# design.net
KiCad netlist of a schematic drawn in Altium Designer
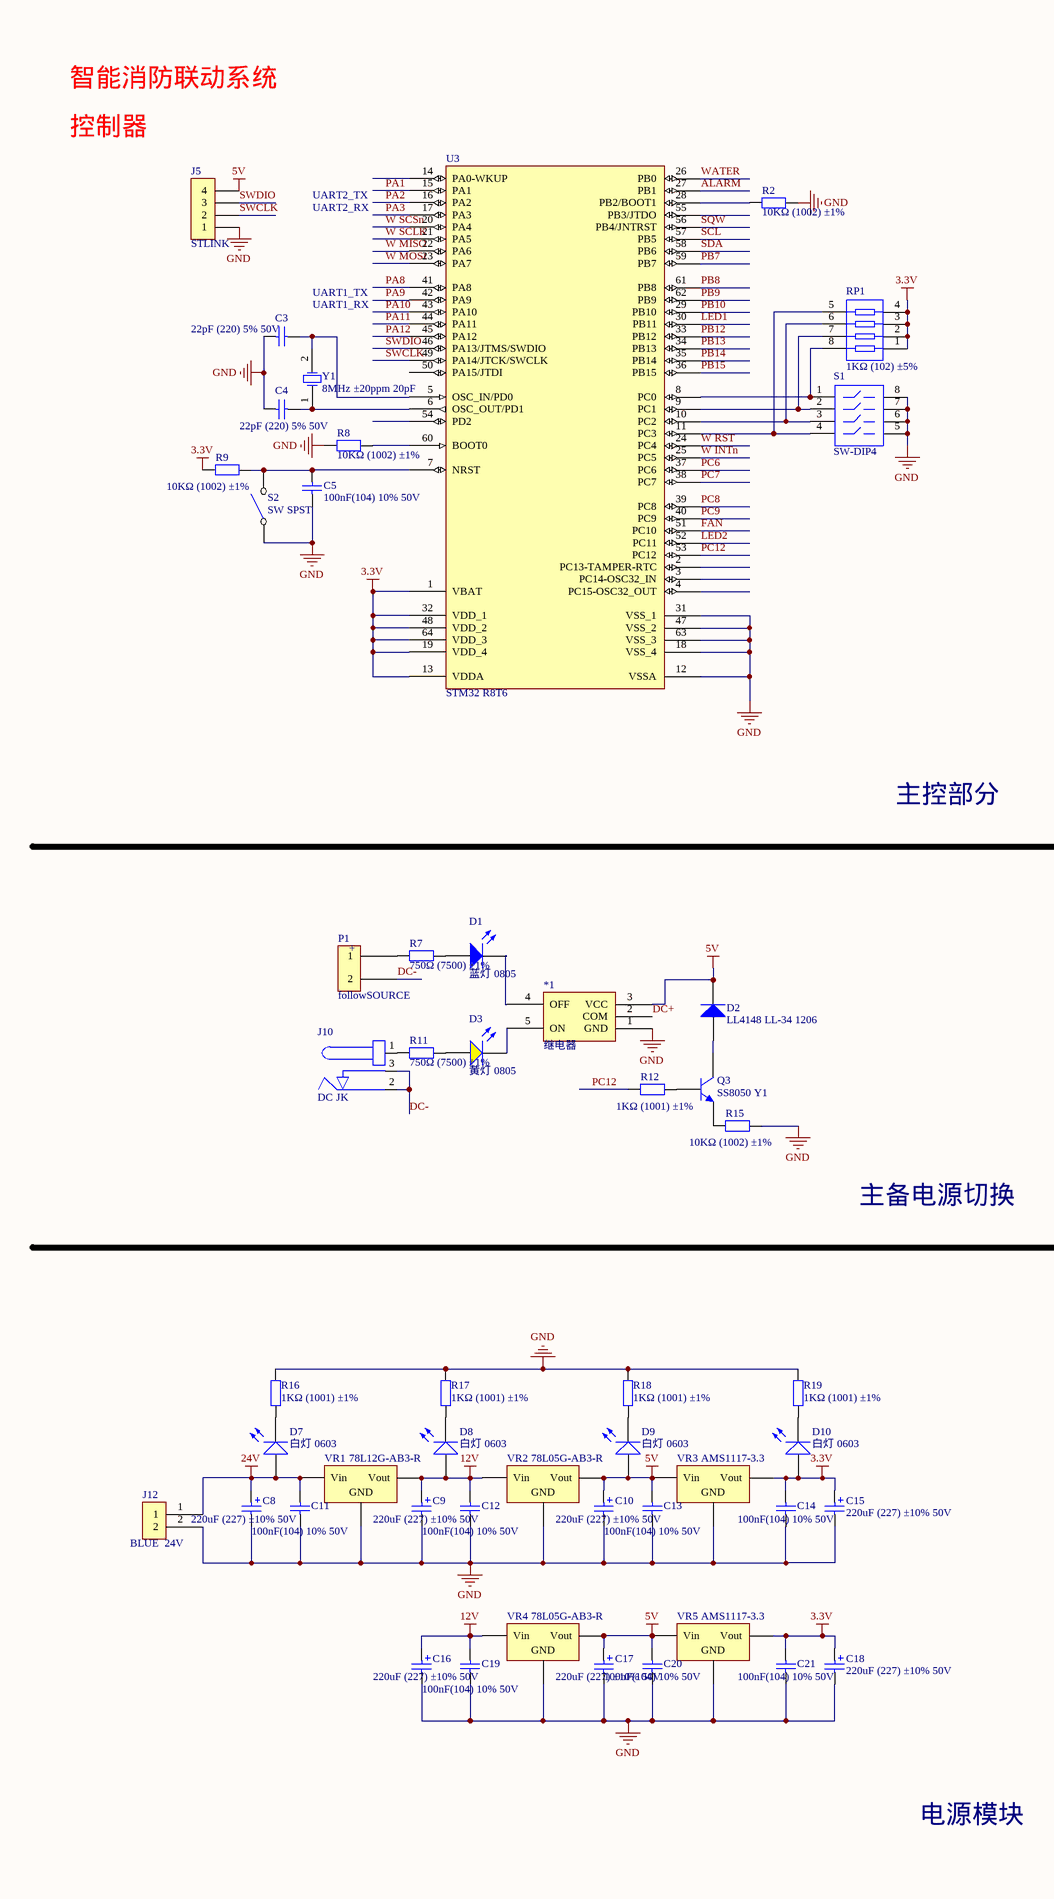
[diagram p0: 控制器.SchDoc, left]
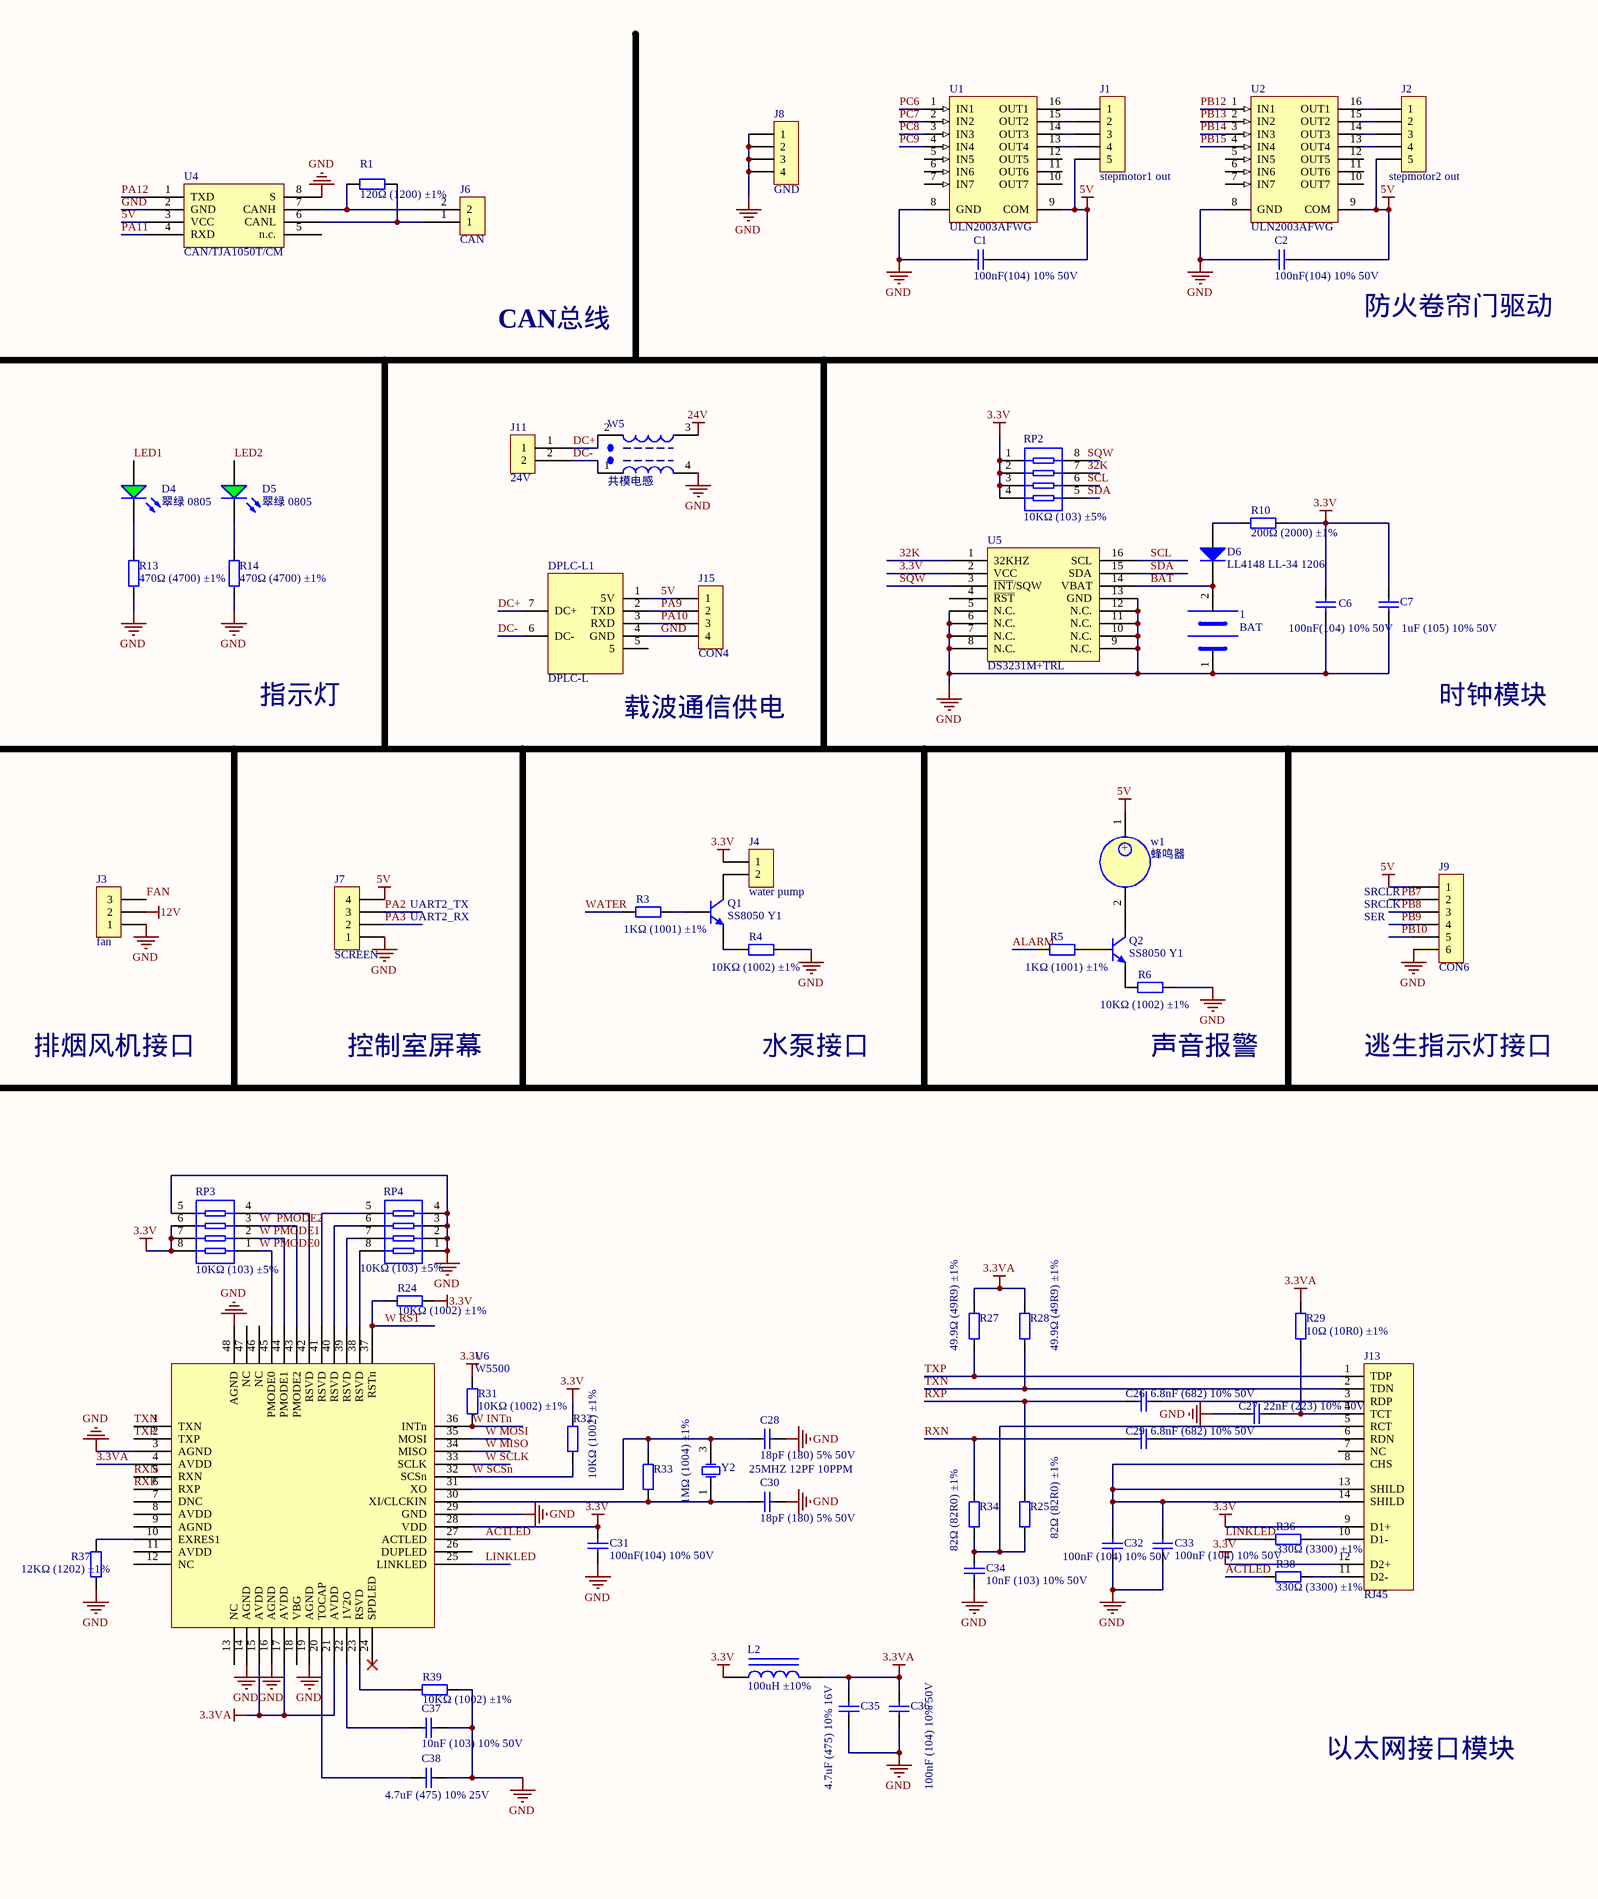
[diagram p1: 控制器.SchDoc, right]

(export (version "E")
  (design (tool "Eeschema 10.0.6"))
  (components
    (comp (ref "*1") (value "继电器") (footprint "RLY-964") (libsource (lib "毕设原理图封装库") (part "继电器")))
    (comp (ref "1") (value "BAT") (footprint "BAT") (libsource (lib "毕设原理图封装库") (part "BAT")))
    (comp (ref "C1")
      (value "100nF(104) 10% 50V")
      (footprint "LC-0805_C")
      (description "贴片电容")
      (libsource (lib "Miscellaneous Devices LC") (part "0805 100nF(104) 10% 50V"))
    )
    (comp (ref "C2")
      (value "100nF(104) 10% 50V")
      (footprint "LC-0805_C")
      (description "贴片电容")
      (libsource (lib "Miscellaneous Devices LC") (part "0805 100nF(104) 10% 50V"))
    )
    (comp (ref "C3")
      (value "22pF (220) 5% 50V")
      (footprint "LC-0805_C")
      (description "贴片电容")
      (libsource (lib "Miscellaneous Devices LC") (part "0805 22pF (220) 5% 50V"))
    )
    (comp (ref "C4")
      (value "22pF (220) 5% 50V")
      (footprint "LC-0805_C")
      (description "贴片电容")
      (libsource (lib "Miscellaneous Devices LC") (part "0805 22pF (220) 5% 50V"))
    )
    (comp (ref "C5")
      (value "100nF(104) 10% 50V")
      (footprint "LC-0805_C")
      (description "贴片电容")
      (libsource (lib "Miscellaneous Devices LC") (part "0805 100nF(104) 10% 50V"))
    )
    (comp (ref "C6")
      (value "100nF(104) 10% 50V")
      (footprint "LC-0805_C")
      (description "贴片电容")
      (libsource (lib "Miscellaneous Devices LC") (part "0805 100nF(104) 10% 50V"))
    )
    (comp (ref "C7")
      (value "1uF (105) 10% 50V")
      (footprint "LC-0805_C")
      (description "贴片电容")
      (libsource (lib "Miscellaneous Devices LC") (part "0805 1uF (105) 10% 50V"))
    )
    (comp (ref "C8")
      (value "220uF (227) ±10% 50V")
      (footprint "LC-CASE-B_3528")
      (description "钽电容")
      (libsource (lib "") (part "3528 100uF (107) 10% 6.3V_1"))
    )
    (comp (ref "C9")
      (value "220uF (227) ±10% 50V")
      (footprint "LC-CASE-B_3528")
      (description "钽电容")
      (libsource (lib "") (part "3528 100uF (107) 10% 6.3V_1"))
    )
    (comp (ref "C10")
      (value "220uF (227) ±10% 50V")
      (footprint "LC-CASE-B_3528")
      (description "钽电容")
      (libsource (lib "") (part "3528 100uF (107) 10% 6.3V_1"))
    )
    (comp (ref "C11")
      (value "100nF(104) 10% 50V")
      (footprint "LC-0805_C")
      (description "贴片电容")
      (libsource (lib "Miscellaneous Devices LC") (part "0805 100nF(104) 10% 50V"))
    )
    (comp (ref "C12")
      (value "100nF(104) 10% 50V")
      (footprint "LC-0805_C")
      (description "贴片电容")
      (libsource (lib "Miscellaneous Devices LC") (part "0805 100nF(104) 10% 50V"))
    )
    (comp (ref "C13")
      (value "100nF(104) 10% 50V")
      (footprint "LC-0805_C")
      (description "贴片电容")
      (libsource (lib "Miscellaneous Devices LC") (part "0805 100nF(104) 10% 50V"))
    )
    (comp (ref "C14")
      (value "100nF(104) 10% 50V")
      (footprint "LC-0805_C")
      (description "贴片电容")
      (libsource (lib "Miscellaneous Devices LC") (part "0805 100nF(104) 10% 50V"))
    )
    (comp (ref "C15")
      (value "220uF (227) ±10% 50V")
      (footprint "LC-CASE-B_3528")
      (description "钽电容")
      (libsource (lib "") (part "3528 100uF (107) 10% 6.3V_1"))
    )
    (comp (ref "C16")
      (value "220uF (227) ±10% 50V")
      (footprint "LC-CASE-B_3528")
      (description "钽电容")
      (libsource (lib "") (part "3528 100uF (107) 10% 6.3V_1"))
    )
    (comp (ref "C17")
      (value "220uF (227) ±10% 50V")
      (footprint "LC-CASE-B_3528")
      (description "钽电容")
      (libsource (lib "") (part "3528 100uF (107) 10% 6.3V_1"))
    )
    (comp (ref "C18")
      (value "220uF (227) ±10% 50V")
      (footprint "LC-CASE-B_3528")
      (description "钽电容")
      (libsource (lib "Miscellaneous Devices LC") (part "3528 100uF (107) 10% 6.3V"))
    )
    (comp (ref "C19")
      (value "100nF(104) 10% 50V")
      (footprint "LC-0805_C")
      (description "贴片电容")
      (libsource (lib "Miscellaneous Devices LC") (part "0805 100nF(104) 10% 50V"))
    )
    (comp (ref "C20")
      (value "100nF(104) 10% 50V")
      (footprint "LC-0805_C")
      (description "贴片电容")
      (libsource (lib "Miscellaneous Devices LC") (part "0805 100nF(104) 10% 50V"))
    )
    (comp (ref "C21")
      (value "100nF(104) 10% 50V")
      (footprint "LC-0805_C")
      (description "贴片电容")
      (libsource (lib "Miscellaneous Devices LC") (part "0805 100nF(104) 10% 50V"))
    )
    (comp (ref "C26")
      (value "6.8nF (682) 10% 50V")
      (footprint "LC-0603_C")
      (description "贴片电容")
      (libsource (lib "Miscellaneous Devices LC") (part "0603 6.8nF (682) 10% 50V"))
    )
    (comp (ref "C27")
      (value "22nF (223) 10% 50V")
      (footprint "LC-0603_C")
      (description "贴片电容")
      (libsource (lib "Miscellaneous Devices LC") (part "0603 22nF (223) 10% 50V"))
    )
    (comp (ref "C28")
      (value "18pF (180) 5% 50V")
      (footprint "LC-0805_C")
      (description "贴片电容")
      (libsource (lib "Miscellaneous Devices LC") (part "0805 18pF (180) 5% 50V"))
    )
    (comp (ref "C29")
      (value "6.8nF (682) 10% 50V")
      (footprint "LC-0603_C")
      (description "贴片电容")
      (libsource (lib "Miscellaneous Devices LC") (part "0603 6.8nF (682) 10% 50V"))
    )
    (comp (ref "C30")
      (value "18pF (180) 5% 50V")
      (footprint "LC-0805_C")
      (description "贴片电容")
      (libsource (lib "Miscellaneous Devices LC") (part "0805 18pF (180) 5% 50V"))
    )
    (comp (ref "C31")
      (value "100nF(104) 10% 50V")
      (footprint "LC-0805_C")
      (description "贴片电容")
      (libsource (lib "Miscellaneous Devices LC") (part "0805 100nF(104) 10% 50V"))
    )
    (comp (ref "C32")
      (value "100nF (104) 10% 50V")
      (footprint "LC-0603_C")
      (description "贴片电容")
      (libsource (lib "Miscellaneous Devices LC") (part "0603 100nF (104) 10% 50V"))
    )
    (comp (ref "C33")
      (value "100nF (104) 10% 50V")
      (footprint "LC-0603_C")
      (description "贴片电容")
      (libsource (lib "Miscellaneous Devices LC") (part "0603 100nF (104) 10% 50V"))
    )
    (comp (ref "C34")
      (value "10nF (103) 10% 50V")
      (footprint "LC-0603_C")
      (description "贴片电容")
      (libsource (lib "Miscellaneous Devices LC") (part "0603 10nF (103) 10% 50V"))
    )
    (comp (ref "C35")
      (value "4.7uF (475) 10% 16V")
      (footprint "LC-0603_C")
      (description "贴片电容")
      (libsource (lib "Miscellaneous Devices LC") (part "0603 4.7uF (475) 10% 16V"))
    )
    (comp (ref "C36")
      (value "100nF (104) 10% 50V")
      (footprint "LC-0603_C")
      (description "贴片电容")
      (libsource (lib "Miscellaneous Devices LC") (part "0603 100nF (104) 10% 50V"))
    )
    (comp (ref "C37")
      (value "10nF (103) 10% 50V")
      (footprint "LC-0805_C")
      (description "贴片电容")
      (libsource (lib "Miscellaneous Devices LC") (part "0805 10nF (103) 10% 50V"))
    )
    (comp (ref "C38")
      (value "4.7uF (475) 10% 25V")
      (footprint "LC-0805_C")
      (description "贴片电容")
      (libsource (lib "Miscellaneous Devices LC") (part "0805 4.7uF (475) 10% 25V"))
    )
    (comp (ref "D1")
      (value "蓝灯 0805")
      (footprint "LC-0805_LED_S1")
      (description "发光二极管")
      (libsource (lib "Miscellaneous Devices LC") (part "0805 蓝灯"))
    )
    (comp (ref "D2")
      (value "LL4148 LL-34 1206")
      (footprint "LC-LL-34")
      (description "开关二极管")
      (libsource (lib "Miscellaneous Devices LC") (part "LL-34 LL4148 LL-34 1206"))
    )
    (comp (ref "D3")
      (value "黄灯 0805")
      (footprint "LC-0805_LED_S1")
      (description "发光二极管")
      (libsource (lib "Miscellaneous Devices LC") (part "0805 黄灯"))
    )
    (comp (ref "D4")
      (value "翠绿 0805")
      (footprint "LC-0805_LED_S1")
      (description "发光二极管")
      (libsource (lib "Miscellaneous Devices LC") (part "0805 翠绿"))
    )
    (comp (ref "D5")
      (value "翠绿 0805")
      (footprint "LC-0805_LED_S1")
      (description "发光二极管")
      (libsource (lib "Miscellaneous Devices LC") (part "0805 翠绿"))
    )
    (comp (ref "D6")
      (value "LL4148 LL-34 1206")
      (footprint "LC-LL-34")
      (description "开关二极管")
      (libsource (lib "Miscellaneous Devices LC") (part "LL-34 LL4148 LL-34 1206"))
    )
    (comp (ref "D7")
      (value "白灯 0603")
      (footprint "LC-0603_LED_S1")
      (description "发光二极管")
      (libsource (lib "Miscellaneous Devices LC") (part "0603 白灯"))
    )
    (comp (ref "D8")
      (value "白灯 0603")
      (footprint "LC-0603_LED_S1")
      (description "发光二极管")
      (libsource (lib "Miscellaneous Devices LC") (part "0603 白灯"))
    )
    (comp (ref "D9")
      (value "白灯 0603")
      (footprint "LC-0603_LED_S1")
      (description "发光二极管")
      (libsource (lib "Miscellaneous Devices LC") (part "0603 白灯"))
    )
    (comp (ref "D10")
      (value "白灯 0603")
      (footprint "LC-0603_LED_S1")
      (description "发光二极管")
      (libsource (lib "Miscellaneous Devices LC") (part "0603 白灯"))
    )
    (comp (ref "DPLC-L1") (value "DPLC-L") (footprint "DPLC-L") (libsource (lib "毕设原理图封装库") (part "DPLC-L")))
    (comp (ref "J1") (value "stepmotor1 out") (footprint "防反插乘5") (libsource (lib "原理图封装库") (part "CON5")))
    (comp (ref "J2") (value "stepmotor2 out") (footprint "防反插乘5") (libsource (lib "原理图封装库") (part "CON5")))
    (comp (ref "J3") (value "fan") (footprint "SIP3") (libsource (lib "原理图封装库") (part "CON3")))
    (comp (ref "J4") (value "water pump") (footprint "SIP2") (libsource (lib "原理图封装库") (part "CON2")))
    (comp (ref "J5") (value "STLINK") (footprint "SIP4") (libsource (lib "毕设原理图封装库") (part "CON4")))
    (comp (ref "J6") (value "CAN") (footprint "蓝端子") (libsource (lib "") (part "蓝端子_2")))
    (comp (ref "J7") (value "SCREEN") (footprint "SIP4") (libsource (lib "毕设原理图封装库") (part "CON4")))
    (comp (ref "J8") (value "GND") (footprint "SIP4") (libsource (lib "") (part "CON4_1")))
    (comp (ref "J9") (value "CON6") (footprint "SIP6") (libsource (lib "毕设原理图封装库") (part "CON6")))
    (comp (ref "J10") (value "DC JK") (footprint "DC") (libsource (lib "Backup of 耳机座") (part "DC JK")))
    (comp (ref "J11") (value "24V") (footprint "蓝端子") (libsource (lib "毕设原理图封装库") (part "蓝端子")))
    (comp (ref "J12") (value "BLUE  24V") (footprint "蓝端子") (libsource (lib "毕设原理图封装库") (part "蓝端子")))
    (comp (ref "J13") (value "RJ45") (footprint "RJ-45_GBE") (libsource (lib "毕设原理图封装库") (part "RJ45")))
    (comp (ref "J15") (value "CON4") (footprint "SIP4") (libsource (lib "") (part "CON4_1")))
    (comp (ref "L2")
      (value "100uH ±10%")
      (footprint "LC-0805_L")
      (description "贴片电感")
      (libsource (lib "Miscellaneous Devices LC") (part "0805 100uH 10%"))
    )
    (comp (ref "P1") (value "followSOURCE") (footprint "蓝端子") (libsource (lib "") (part "蓝端子_1")))
    (comp (ref "Q1")
      (value "SS8050 Y1")
      (footprint "LC-SOT-23(SOT-23-3)")
      (description "三极管")
      (libsource (lib "Miscellaneous Devices LC") (part "SOT-23 SS8050 Y1"))
    )
    (comp (ref "Q2")
      (value "SS8050 Y1")
      (footprint "LC-SOT-23(SOT-23-3)")
      (description "三极管")
      (libsource (lib "Miscellaneous Devices LC") (part "SOT-23 SS8050 Y1"))
    )
    (comp (ref "Q3")
      (value "SS8050 Y1")
      (footprint "LC-SOT-23(SOT-23-3)")
      (description "三极管")
      (libsource (lib "Miscellaneous Devices LC") (part "SOT-23 SS8050 Y1"))
    )
    (comp (ref "R1")
      (value "120Ω (1200) ±1%")
      (footprint "LC-0805_R")
      (description "贴片电阻")
      (libsource (lib "Miscellaneous Devices LC") (part "0805 120Ω (1200) 1%"))
    )
    (comp (ref "R2")
      (value "10KΩ (1002) ±1%")
      (footprint "LC-0805_R")
      (description "贴片电阻")
      (libsource (lib "Miscellaneous Devices LC") (part "0805 10KΩ (1002) 1%"))
    )
    (comp (ref "R3")
      (value "1KΩ (1001) ±1%")
      (footprint "LC-0805_R")
      (description "贴片电阻")
      (libsource (lib "Miscellaneous Devices LC") (part "0805 1KΩ (1001) 1%"))
    )
    (comp (ref "R4")
      (value "10KΩ (1002) ±1%")
      (footprint "LC-0805_R")
      (description "贴片电阻")
      (libsource (lib "Miscellaneous Devices LC") (part "0805 10KΩ (1002) 1%"))
    )
    (comp (ref "R5")
      (value "1KΩ (1001) ±1%")
      (footprint "LC-0805_R")
      (description "贴片电阻")
      (libsource (lib "Miscellaneous Devices LC") (part "0805 1KΩ (1001) 1%"))
    )
    (comp (ref "R6")
      (value "10KΩ (1002) ±1%")
      (footprint "LC-0805_R")
      (description "贴片电阻")
      (libsource (lib "Miscellaneous Devices LC") (part "0805 10KΩ (1002) 1%"))
    )
    (comp (ref "R7")
      (value "750Ω (7500) ±1%")
      (footprint "LC-0805_R")
      (description "贴片电阻")
      (libsource (lib "Miscellaneous Devices LC") (part "0805 750Ω (7500) 1%"))
    )
    (comp (ref "R8")
      (value "10KΩ (1002) ±1%")
      (footprint "LC-0805_R")
      (description "贴片电阻")
      (libsource (lib "Miscellaneous Devices LC") (part "0805 10KΩ (1002) 1%"))
    )
    (comp (ref "R9")
      (value "10KΩ (1002) ±1%")
      (footprint "LC-0805_R")
      (description "贴片电阻")
      (libsource (lib "Miscellaneous Devices LC") (part "0805 10KΩ (1002) 1%"))
    )
    (comp (ref "R10")
      (value "200Ω (2000) ±1%")
      (footprint "LC-0805_R")
      (description "贴片电阻")
      (libsource (lib "Miscellaneous Devices LC") (part "0805 200Ω (2000) 1%"))
    )
    (comp (ref "R11")
      (value "750Ω (7500) ±1%")
      (footprint "LC-0805_R")
      (description "贴片电阻")
      (libsource (lib "Miscellaneous Devices LC") (part "0805 750Ω (7500) 1%"))
    )
    (comp (ref "R12")
      (value "1KΩ (1001) ±1%")
      (footprint "LC-0805_R")
      (description "贴片电阻")
      (libsource (lib "Miscellaneous Devices LC") (part "0805 1KΩ (1001) 1%"))
    )
    (comp (ref "R13")
      (value "470Ω (4700) ±1%")
      (footprint "LC-0805_R")
      (description "贴片电阻")
      (libsource (lib "Miscellaneous Devices LC") (part "0805 470Ω (4700) 1%"))
    )
    (comp (ref "R14")
      (value "470Ω (4700) ±1%")
      (footprint "LC-0805_R")
      (description "贴片电阻")
      (libsource (lib "Miscellaneous Devices LC") (part "0805 470Ω (4700) 1%"))
    )
    (comp (ref "R15")
      (value "10KΩ (1002) ±1%")
      (footprint "LC-0805_R")
      (description "贴片电阻")
      (libsource (lib "Miscellaneous Devices LC") (part "0805 10KΩ (1002) 1%"))
    )
    (comp (ref "R16")
      (value "1KΩ (1001) ±1%")
      (footprint "LC-0603_R")
      (description "贴片电阻")
      (libsource (lib "Miscellaneous Devices LC") (part "0603 1KΩ (1001) 1%"))
    )
    (comp (ref "R17")
      (value "1KΩ (1001) ±1%")
      (footprint "LC-0603_R")
      (description "贴片电阻")
      (libsource (lib "Miscellaneous Devices LC") (part "0603 1KΩ (1001) 1%"))
    )
    (comp (ref "R18")
      (value "1KΩ (1001) ±1%")
      (footprint "LC-0603_R")
      (description "贴片电阻")
      (libsource (lib "Miscellaneous Devices LC") (part "0603 1KΩ (1001) 1%"))
    )
    (comp (ref "R19")
      (value "1KΩ (1001) ±1%")
      (footprint "LC-0603_R")
      (description "贴片电阻")
      (libsource (lib "Miscellaneous Devices LC") (part "0603 1KΩ (1001) 1%"))
    )
    (comp (ref "R24")
      (value "10KΩ (1002) ±1%")
      (footprint "LC-0805_R")
      (description "贴片电阻")
      (libsource (lib "Miscellaneous Devices LC") (part "0805 10KΩ (1002) 1%"))
    )
    (comp (ref "R25")
      (value "82Ω (82R0) ±1%")
      (footprint "LC-0603_R")
      (description "贴片电阻")
      (libsource (lib "Miscellaneous Devices LC") (part "0603 82Ω (82R0) 1%"))
    )
    (comp (ref "R27")
      (value "49.9Ω (49R9) ±1%")
      (footprint "LC-0603_R")
      (description "贴片电阻")
      (libsource (lib "Miscellaneous Devices LC") (part "0603 49.9Ω (49R9) 1%"))
    )
    (comp (ref "R28")
      (value "49.9Ω (49R9) ±1%")
      (footprint "LC-0603_R")
      (description "贴片电阻")
      (libsource (lib "Miscellaneous Devices LC") (part "0603 49.9Ω (49R9) 1%"))
    )
    (comp (ref "R29")
      (value "10Ω (10R0) ±1%")
      (footprint "LC-0805_R")
      (description "贴片电阻")
      (libsource (lib "Miscellaneous Devices LC") (part "0805 10Ω (10R0) 1%"))
    )
    (comp (ref "R31")
      (value "10KΩ (1002) ±1%")
      (footprint "LC-0805_R")
      (description "贴片电阻")
      (libsource (lib "") (part "0805 10KΩ (1002) 1%_1"))
    )
    (comp (ref "R32")
      (value "10KΩ (1002) ±1%")
      (footprint "LC-0805_R")
      (description "贴片电阻")
      (libsource (lib "") (part "0805 10KΩ (1002) 1%_1"))
    )
    (comp (ref "R33")
      (value "1MΩ (1004) ±1%")
      (footprint "LC-0805_R")
      (description "贴片电阻")
      (libsource (lib "Miscellaneous Devices LC") (part "0805 1MΩ (1004) 1%"))
    )
    (comp (ref "R34")
      (value "82Ω (82R0) ±1%")
      (footprint "LC-0603_R")
      (description "贴片电阻")
      (libsource (lib "Miscellaneous Devices LC") (part "0603 82Ω (82R0) 1%"))
    )
    (comp (ref "R36")
      (value "330Ω (3300) ±1%")
      (footprint "LC-0603_R")
      (description "贴片电阻")
      (libsource (lib "Miscellaneous Devices LC") (part "0603 330Ω (3300) 1%"))
    )
    (comp (ref "R37")
      (value "12KΩ (1202) ±1%")
      (footprint "LC-0805_R")
      (description "贴片电阻")
      (libsource (lib "Miscellaneous Devices LC") (part "0805 12KΩ (1202) 1%"))
    )
    (comp (ref "R38")
      (value "330Ω (3300) ±1%")
      (footprint "LC-0603_R")
      (description "贴片电阻")
      (libsource (lib "Miscellaneous Devices LC") (part "0603 330Ω (3300) 1%"))
    )
    (comp (ref "R39")
      (value "10KΩ (1002) ±1%")
      (footprint "LC-0805_R")
      (description "贴片电阻")
      (libsource (lib "Miscellaneous Devices LC") (part "0805 10KΩ (1002) 1%"))
    )
    (comp (ref "RP1")
      (value "1KΩ (102) ±5%")
      (footprint "LC-0603_Rx4")
      (description "贴片排阻")
      (libsource (lib "Miscellaneous Devices LC") (part "0603*4  1KΩ (102) 5%"))
    )
    (comp (ref "RP2")
      (value "10KΩ (103) ±5%")
      (footprint "LC-0603_Rx4")
      (description "贴片排阻")
      (libsource (lib "Miscellaneous Devices LC") (part "0603*4  10KΩ (103) 5%"))
    )
    (comp (ref "RP3")
      (value "10KΩ (103) ±5%")
      (footprint "LC-0603_Rx4")
      (description "贴片排阻")
      (libsource (lib "Miscellaneous Devices LC") (part "0603*4  10KΩ (103) 5%"))
    )
    (comp (ref "RP4")
      (value "10KΩ (103) ±5%")
      (footprint "LC-0603_Rx4")
      (description "贴片排阻")
      (libsource (lib "Miscellaneous Devices LC") (part "0603*4  10KΩ (103) 5%"))
    )
    (comp (ref "S1")
      (value "SW-DIP4")
      (footprint "4位拨码开关")
      (description "4位拨码开关")
      (libsource (lib "毕设原理图封装库") (part "SW-DIP4"))
    )
    (comp (ref "S2")
      (value "SW SPST")
      (footprint "单片机小按键")
      (description "单刀单掷开关")
      (libsource (lib "毕设原理图封装库") (part "SW SPST"))
    )
    (comp (ref "U1")
      (value "ULN2003AFWG")
      (footprint "LC-SOIC-16_150mil")
      (description "大电流驱动")
      (libsource (lib "Miscellaneous Devices LC") (part "ULN2003AFWG"))
    )
    (comp (ref "U2")
      (value "ULN2003AFWG")
      (footprint "LC-SOIC-16_150mil")
      (description "大电流驱动")
      (libsource (lib "Miscellaneous Devices LC") (part "ULN2003AFWG"))
    )
    (comp (ref "U3")
      (value "STM32 R8T6")
      (footprint "LC-LQFP-64_10x10x05P")
      (libsource (lib "毕设原理图封装库") (part "STM32 R8T6"))
    )
    (comp (ref "U4")
      (value "CAN/TJA1050T/CM")
      (footprint "LC-SOIC-8_150mil")
      (description "CAN")
      (libsource (lib "Miscellaneous Devices LC") (part "CAN/TJA1050T/CM"))
    )
    (comp (ref "U5")
      (value "DS3231M+TRL")
      (footprint "LC-SOIC-16_300mil")
      (description "实时时钟")
      (libsource (lib "Miscellaneous Devices LC") (part "DS3231M+TRL"))
    )
    (comp (ref "U6")
      (value "W5500")
      (footprint "LC-LQFP-48_7x7x05P")
      (description "以太网")
      (libsource (lib "Miscellaneous Devices LC") (part "W5500"))
    )
    (comp (ref "VR1")
      (value "78L12G-AB3-R")
      (footprint "LC-SOT-89(SOT-89-3)")
      (description "低压差线性稳压(LDO)")
      (libsource (lib "Miscellaneous Devices LC") (part "SOT-89 78L12G-AB3-R"))
    )
    (comp (ref "VR2")
      (value "78L05G-AB3-R")
      (footprint "LC-SOT-89(SOT-89-3)")
      (description "低压差线性稳压(LDO)")
      (libsource (lib "Miscellaneous Devices LC") (part "SOT-89 78L05G-AB3-R"))
    )
    (comp (ref "VR3")
      (value "AMS1117-3.3")
      (footprint "LC-SOT-223")
      (description "低压差线性稳压(LDO)")
      (libsource (lib "Miscellaneous Devices LC") (part "SOT-223 AMS1117-3.3"))
    )
    (comp (ref "VR4")
      (value "78L05G-AB3-R")
      (footprint "LC-SOT-89(SOT-89-3)")
      (description "低压差线性稳压(LDO)")
      (libsource (lib "Miscellaneous Devices LC") (part "SOT-89 78L05G-AB3-R"))
    )
    (comp (ref "VR5")
      (value "AMS1117-3.3")
      (footprint "LC-SOT-223")
      (description "低压差线性稳压(LDO)")
      (libsource (lib "Miscellaneous Devices LC") (part "SOT-223 AMS1117-3.3"))
    )
    (comp (ref "w1") (value "蜂鸣器") (footprint "蜂鸣器") (libsource (lib "毕设原理图封装库") (part "蜂鸣器")))
    (comp (ref "W5") (value "共模电感") (footprint "共模电感") (libsource (lib "毕设原理图封装库") (part "共模电感")))
    (comp (ref "Y1")
      (value "8MHz ±20ppm 20pF")
      (footprint "LC-SMD-5032_2P")
      (description "贴片晶振")
      (libsource (lib "Miscellaneous Devices LC") (part "SMD-5032_2P 8MHz 20ppm 20pF"))
    )
    (comp (ref "Y2")
      (value "25MHZ 12PF 10PPM")
      (footprint "LC-SMD-3225_4P")
      (description "贴片晶振")
      (libsource (lib "Miscellaneous Devices LC") (part "SMD-3225_4P  25MHZ 12PF 10PPM"))
    )
  )
  (nets
    (net (code "1") (name "/32K") (class "Default")
      (node (ref "RP2") (pin "7") (pinfunction "7_7") (pintype "passive"))
      (node (ref "U5") (pin "1") (pinfunction "32KHZ_1") (pintype "passive"))
    )
    (net (code "2") (name "/ACTLED") (class "Default")
      (node (ref "R38") (pin "1") (pinfunction "1_1") (pintype "passive"))
      (node (ref "U6") (pin "27") (pinfunction "ACTLED_27") (pintype "passive"))
    )
    (net (code "3") (name "/ALARM") (class "Default")
      (node (ref "R5") (pin "1") (pinfunction "1_1") (pintype "passive"))
      (node (ref "U3") (pin "27") (pinfunction "PB1_27") (pintype "bidirectional"))
    )
    (net (code "4") (name "/BAT") (class "Default")
      (node (ref "1") (pin "2") (pinfunction "2_2") (pintype "passive"))
      (node (ref "D6") (pin "2") (pinfunction "K_2") (pintype "passive"))
      (node (ref "U5") (pin "14") (pinfunction "VBAT_14") (pintype "passive"))
    )
    (net (code "5") (name "/DC+") (class "Default")
      (node (ref "*1") (pin "2") (pinfunction "COM_2") (pintype "passive"))
      (node (ref "DPLC-L1") (pin "7") (pinfunction "DC+_7") (pintype "passive"))
      (node (ref "J11") (pin "1") (pinfunction "1_1") (pintype "passive"))
      (node (ref "W5") (pin "2") (pinfunction "2_2") (pintype "passive"))
    )
    (net (code "6") (name "/DC-") (class "Default")
      (node (ref "DPLC-L1") (pin "6") (pinfunction "DC-_6") (pintype "passive"))
      (node (ref "J10") (pin "2") (pinfunction "GND_2") (pintype "passive"))
      (node (ref "J10") (pin "3") (pinfunction "GND_3") (pintype "passive"))
      (node (ref "J11") (pin "2") (pinfunction "2_2") (pintype "passive"))
      (node (ref "P1") (pin "2") (pinfunction "2_2") (pintype "passive"))
      (node (ref "W5") (pin "1") (pinfunction "1_1") (pintype "passive"))
    )
    (net (code "7") (name "/FAN") (class "Default")
      (node (ref "J3") (pin "3") (pinfunction "3_3") (pintype "passive"))
      (node (ref "U3") (pin "51") (pinfunction "PC10_51") (pintype "bidirectional"))
    )
    (net (code "8") (name "/LED1") (class "Default")
      (node (ref "D4") (pin "A") (pinfunction "A_A") (pintype "passive"))
      (node (ref "U3") (pin "30") (pinfunction "PB11_30") (pintype "bidirectional"))
    )
    (net (code "9") (name "/LED2") (class "Default")
      (node (ref "D5") (pin "A") (pinfunction "A_A") (pintype "passive"))
      (node (ref "U3") (pin "52") (pinfunction "PC11_52") (pintype "bidirectional"))
    )
    (net (code "10") (name "/LINKLED") (class "Default")
      (node (ref "R36") (pin "1") (pinfunction "1_1") (pintype "passive"))
      (node (ref "U6") (pin "25") (pinfunction "LINKLED_25") (pintype "passive"))
    )
    (net (code "11") (name "/PA1") (class "Default")
      (node (ref "U3") (pin "15") (pinfunction "PA1_15") (pintype "bidirectional"))
    )
    (net (code "12") (name "/PA2") (class "Default")
      (node (ref "J7") (pin "3") (pinfunction "3_3") (pintype "passive"))
      (node (ref "U3") (pin "16") (pinfunction "PA2_16") (pintype "bidirectional"))
    )
    (net (code "13") (name "/PA3") (class "Default")
      (node (ref "J7") (pin "2") (pinfunction "2_2") (pintype "passive"))
      (node (ref "U3") (pin "17") (pinfunction "PA3_17") (pintype "bidirectional"))
    )
    (net (code "14") (name "/PA8") (class "Default")
      (node (ref "U3") (pin "41") (pinfunction "PA8_41") (pintype "bidirectional"))
    )
    (net (code "15") (name "/PA9") (class "Default")
      (node (ref "DPLC-L1") (pin "2") (pinfunction "TXD_2") (pintype "passive"))
      (node (ref "J15") (pin "2") (pinfunction "2_2") (pintype "passive"))
      (node (ref "U3") (pin "42") (pinfunction "PA9_42") (pintype "bidirectional"))
    )
    (net (code "16") (name "/PA10") (class "Default")
      (node (ref "DPLC-L1") (pin "3") (pinfunction "RXD_3") (pintype "passive"))
      (node (ref "J15") (pin "3") (pinfunction "3_3") (pintype "passive"))
      (node (ref "U3") (pin "43") (pinfunction "PA10_43") (pintype "bidirectional"))
    )
    (net (code "17") (name "/PA11") (class "Default")
      (node (ref "U3") (pin "44") (pinfunction "PA11_44") (pintype "bidirectional"))
      (node (ref "U4") (pin "4") (pinfunction "RXD_4") (pintype "passive"))
    )
    (net (code "18") (name "/PA12") (class "Default")
      (node (ref "U3") (pin "45") (pinfunction "PA12_45") (pintype "bidirectional"))
      (node (ref "U4") (pin "1") (pinfunction "TXD_1") (pintype "passive"))
    )
    (net (code "19") (name "/PB7") (class "Default")
      (node (ref "J9") (pin "2") (pinfunction "2_2") (pintype "passive"))
      (node (ref "U3") (pin "59") (pinfunction "PB7_59") (pintype "bidirectional"))
    )
    (net (code "20") (name "/PB8") (class "Default")
      (node (ref "J9") (pin "3") (pinfunction "3_3") (pintype "passive"))
      (node (ref "U3") (pin "61") (pinfunction "PB8_61") (pintype "bidirectional"))
    )
    (net (code "21") (name "/PB9") (class "Default")
      (node (ref "J9") (pin "4") (pinfunction "4_4") (pintype "passive"))
      (node (ref "U3") (pin "62") (pinfunction "PB9_62") (pintype "bidirectional"))
    )
    (net (code "22") (name "/PB10") (class "Default")
      (node (ref "J9") (pin "5") (pinfunction "5_5") (pintype "passive"))
      (node (ref "U3") (pin "29") (pinfunction "PB10_29") (pintype "bidirectional"))
    )
    (net (code "23") (name "/PB12") (class "Default")
      (node (ref "U2") (pin "1") (pinfunction "IN1_1") (pintype "input"))
      (node (ref "U3") (pin "33") (pinfunction "PB12_33") (pintype "bidirectional"))
    )
    (net (code "24") (name "/PB13") (class "Default")
      (node (ref "U2") (pin "2") (pinfunction "IN2_2") (pintype "input"))
      (node (ref "U3") (pin "34") (pinfunction "PB13_34") (pintype "bidirectional"))
    )
    (net (code "25") (name "/PB14") (class "Default")
      (node (ref "U2") (pin "3") (pinfunction "IN3_3") (pintype "input"))
      (node (ref "U3") (pin "35") (pinfunction "PB14_35") (pintype "bidirectional"))
    )
    (net (code "26") (name "/PB15") (class "Default")
      (node (ref "U2") (pin "4") (pinfunction "IN4_4") (pintype "input"))
      (node (ref "U3") (pin "36") (pinfunction "PB15_36") (pintype "bidirectional"))
    )
    (net (code "27") (name "/PC6") (class "Default")
      (node (ref "U1") (pin "1") (pinfunction "IN1_1") (pintype "input"))
      (node (ref "U3") (pin "37") (pinfunction "PC6_37") (pintype "bidirectional"))
    )
    (net (code "28") (name "/PC7") (class "Default")
      (node (ref "U1") (pin "2") (pinfunction "IN2_2") (pintype "input"))
      (node (ref "U3") (pin "38") (pinfunction "PC7_38") (pintype "bidirectional"))
    )
    (net (code "29") (name "/PC8") (class "Default")
      (node (ref "U1") (pin "3") (pinfunction "IN3_3") (pintype "input"))
      (node (ref "U3") (pin "39") (pinfunction "PC8_39") (pintype "bidirectional"))
    )
    (net (code "30") (name "/PC9") (class "Default")
      (node (ref "U1") (pin "4") (pinfunction "IN4_4") (pintype "input"))
      (node (ref "U3") (pin "40") (pinfunction "PC9_40") (pintype "bidirectional"))
    )
    (net (code "31") (name "/PC12") (class "Default")
      (node (ref "R12") (pin "1") (pinfunction "1_1") (pintype "passive"))
      (node (ref "U3") (pin "53") (pinfunction "PC12_53") (pintype "bidirectional"))
    )
    (net (code "32") (name "/RXN") (class "Default")
      (node (ref "C29") (pin "1") (pinfunction "1_1") (pintype "passive"))
      (node (ref "R34") (pin "2") (pinfunction "2_2") (pintype "passive"))
      (node (ref "U6") (pin "5") (pinfunction "RXN_5") (pintype "passive"))
    )
    (net (code "33") (name "/RXP") (class "Default")
      (node (ref "C26") (pin "1") (pinfunction "1_1") (pintype "passive"))
      (node (ref "R25") (pin "2") (pinfunction "2_2") (pintype "passive"))
      (node (ref "U6") (pin "6") (pinfunction "RXP_6") (pintype "passive"))
    )
    (net (code "34") (name "/SCL") (class "Default")
      (node (ref "RP2") (pin "6") (pinfunction "6_6") (pintype "passive"))
      (node (ref "U3") (pin "57") (pinfunction "PB5_57") (pintype "bidirectional"))
      (node (ref "U5") (pin "16") (pinfunction "SCL_16") (pintype "passive"))
    )
    (net (code "35") (name "/SDA") (class "Default")
      (node (ref "RP2") (pin "5") (pinfunction "5_5") (pintype "passive"))
      (node (ref "U3") (pin "58") (pinfunction "PB6_58") (pintype "bidirectional"))
      (node (ref "U5") (pin "15") (pinfunction "SDA_15") (pintype "passive"))
    )
    (net (code "36") (name "/SQW") (class "Default")
      (node (ref "RP2") (pin "8") (pinfunction "8_8") (pintype "passive"))
      (node (ref "U3") (pin "56") (pinfunction "PB4/JNTRST_56") (pintype "bidirectional"))
      (node (ref "U5") (pin "3") (pinfunction "~{INT}/SQW_3") (pintype "passive"))
    )
    (net (code "37") (name "/SWCLK") (class "Default")
      (node (ref "J5") (pin "2") (pinfunction "2_2") (pintype "passive"))
      (node (ref "U3") (pin "49") (pinfunction "PA14/JTCK/SWCLK_49") (pintype "bidirectional"))
    )
    (net (code "38") (name "/SWDIO") (class "Default")
      (node (ref "J5") (pin "3") (pinfunction "3_3") (pintype "passive"))
      (node (ref "U3") (pin "46") (pinfunction "PA13/JTMS/SWDIO_46") (pintype "bidirectional"))
    )
    (net (code "39") (name "/TXN") (class "Default")
      (node (ref "J13") (pin "2") (pinfunction "TDN_2") (pintype "passive"))
      (node (ref "R28") (pin "1") (pinfunction "1_1") (pintype "passive"))
      (node (ref "U6") (pin "1") (pinfunction "TXN_1") (pintype "passive"))
    )
    (net (code "40") (name "/TXP") (class "Default")
      (node (ref "J13") (pin "1") (pinfunction "TDP_1") (pintype "passive"))
      (node (ref "R27") (pin "1") (pinfunction "1_1") (pintype "passive"))
      (node (ref "U6") (pin "2") (pinfunction "TXP_2") (pintype "passive"))
    )
    (net (code "41") (name "/W  PMODE2") (class "Default")
      (node (ref "RP3") (pin "3") (pinfunction "3_3") (pintype "passive"))
      (node (ref "U6") (pin "43") (pinfunction "PMODE2_43") (pintype "passive"))
    )
    (net (code "42") (name "/W INTn") (class "Default")
      (node (ref "R31") (pin "1") (pinfunction "1_1") (pintype "passive"))
      (node (ref "U3") (pin "25") (pinfunction "PC5_25") (pintype "bidirectional"))
      (node (ref "U6") (pin "36") (pinfunction "INTn_36") (pintype "passive"))
    )
    (net (code "43") (name "/W MISO") (class "Default")
      (node (ref "U3") (pin "22") (pinfunction "PA6_22") (pintype "bidirectional"))
      (node (ref "U6") (pin "34") (pinfunction "MISO_34") (pintype "passive"))
    )
    (net (code "44") (name "/W MOSI") (class "Default")
      (node (ref "U3") (pin "23") (pinfunction "PA7_23") (pintype "bidirectional"))
      (node (ref "U6") (pin "35") (pinfunction "MOSI_35") (pintype "passive"))
    )
    (net (code "45") (name "/W PMODE0") (class "Default")
      (node (ref "RP3") (pin "1") (pinfunction "1_1") (pintype "passive"))
      (node (ref "U6") (pin "45") (pinfunction "PMODE0_45") (pintype "passive"))
    )
    (net (code "46") (name "/W PMODE1") (class "Default")
      (node (ref "RP3") (pin "2") (pinfunction "2_2") (pintype "passive"))
      (node (ref "U6") (pin "44") (pinfunction "PMODE1_44") (pintype "passive"))
    )
    (net (code "47") (name "/W RST") (class "Default")
      (node (ref "R24") (pin "1") (pinfunction "1_1") (pintype "passive"))
      (node (ref "U3") (pin "24") (pinfunction "PC4_24") (pintype "bidirectional"))
      (node (ref "U6") (pin "37") (pinfunction "RSTn_37") (pintype "passive"))
    )
    (net (code "48") (name "/W SCLK") (class "Default")
      (node (ref "U3") (pin "21") (pinfunction "PA5_21") (pintype "bidirectional"))
      (node (ref "U6") (pin "33") (pinfunction "SCLK_33") (pintype "passive"))
    )
    (net (code "49") (name "/W SCSn") (class "Default")
      (node (ref "R32") (pin "1") (pinfunction "1_1") (pintype "passive"))
      (node (ref "U3") (pin "20") (pinfunction "PA4_20") (pintype "bidirectional"))
      (node (ref "U6") (pin "32") (pinfunction "SCSn_32") (pintype "passive"))
    )
    (net (code "50") (name "/WATER") (class "Default")
      (node (ref "R3") (pin "1") (pinfunction "1_1") (pintype "passive"))
      (node (ref "U3") (pin "26") (pinfunction "PB0_26") (pintype "bidirectional"))
    )
    (net (code "51") (name "3.3V") (class "Default")
      (node (ref "C14") (pin "1") (pinfunction "1_1") (pintype "passive"))
      (node (ref "C15") (pin "1") (pinfunction "1_1") (pintype "passive"))
      (node (ref "C18") (pin "2") (pinfunction "2_2") (pintype "passive"))
      (node (ref "C21") (pin "1") (pinfunction "1_1") (pintype "passive"))
      (node (ref "C31") (pin "2") (pinfunction "2_2") (pintype "passive"))
      (node (ref "C6") (pin "2") (pinfunction "2_2") (pintype "passive"))
      (node (ref "C7") (pin "2") (pinfunction "2_2") (pintype "passive"))
      (node (ref "D10") (pin "A") (pinfunction "A_A") (pintype "passive"))
      (node (ref "J13") (pin "12") (pinfunction "D2+_12") (pintype "passive"))
      (node (ref "J13") (pin "9") (pinfunction "D1+_9") (pintype "passive"))
      (node (ref "J4") (pin "1") (pinfunction "1_1") (pintype "passive"))
      (node (ref "L2") (pin "1") (pinfunction "1_1") (pintype "passive"))
      (node (ref "R10") (pin "1") (pinfunction "1_1") (pintype "passive"))
      (node (ref "R24") (pin "2") (pinfunction "2_2") (pintype "passive"))
      (node (ref "R31") (pin "2") (pinfunction "2_2") (pintype "passive"))
      (node (ref "R32") (pin "2") (pinfunction "2_2") (pintype "passive"))
      (node (ref "R9") (pin "1") (pinfunction "1_1") (pintype "passive"))
      (node (ref "RP1") (pin "1") (pinfunction "1_1") (pintype "passive"))
      (node (ref "RP1") (pin "2") (pinfunction "2_2") (pintype "passive"))
      (node (ref "RP1") (pin "3") (pinfunction "3_3") (pintype "passive"))
      (node (ref "RP1") (pin "4") (pinfunction "4_4") (pintype "passive"))
      (node (ref "RP2") (pin "1") (pinfunction "1_1") (pintype "passive"))
      (node (ref "RP2") (pin "2") (pinfunction "2_2") (pintype "passive"))
      (node (ref "RP2") (pin "3") (pinfunction "3_3") (pintype "passive"))
      (node (ref "RP2") (pin "4") (pinfunction "4_4") (pintype "passive"))
      (node (ref "RP3") (pin "6") (pinfunction "6_6") (pintype "passive"))
      (node (ref "RP3") (pin "7") (pinfunction "7_7") (pintype "passive"))
      (node (ref "RP3") (pin "8") (pinfunction "8_8") (pintype "passive"))
      (node (ref "U3") (pin "1") (pinfunction "VBAT_1") (pintype "power_in"))
      (node (ref "U3") (pin "13") (pinfunction "VDDA_13") (pintype "power_in"))
      (node (ref "U3") (pin "19") (pinfunction "VDD_4_19") (pintype "power_in"))
      (node (ref "U3") (pin "32") (pinfunction "VDD_1_32") (pintype "power_in"))
      (node (ref "U3") (pin "48") (pinfunction "VDD_2_48") (pintype "power_in"))
      (node (ref "U3") (pin "64") (pinfunction "VDD_3_64") (pintype "power_in"))
      (node (ref "U5") (pin "2") (pinfunction "VCC_2") (pintype "passive"))
      (node (ref "U6") (pin "28") (pinfunction "VDD_28") (pintype "passive"))
      (node (ref "VR3") (pin "2") (pinfunction "Vout_2") (pintype "passive"))
      (node (ref "VR5") (pin "2") (pinfunction "Vout_2") (pintype "passive"))
    )
    (net (code "52") (name "3.3VA") (class "Default")
      (node (ref "C35") (pin "2") (pinfunction "2_2") (pintype "passive"))
      (node (ref "C36") (pin "2") (pinfunction "2_2") (pintype "passive"))
      (node (ref "L2") (pin "2") (pinfunction "2_2") (pintype "passive"))
      (node (ref "R27") (pin "2") (pinfunction "2_2") (pintype "passive"))
      (node (ref "R28") (pin "2") (pinfunction "2_2") (pintype "passive"))
      (node (ref "R29") (pin "2") (pinfunction "2_2") (pintype "passive"))
      (node (ref "U6") (pin "15") (pinfunction "AVDD_15") (pintype "passive"))
      (node (ref "U6") (pin "17") (pinfunction "AVDD_17") (pintype "passive"))
      (node (ref "U6") (pin "21") (pinfunction "AVDD_21") (pintype "passive"))
      (node (ref "U6") (pin "4") (pinfunction "AVDD_4") (pintype "passive"))
    )
    (net (code "53") (name "5V") (class "Default")
      (node (ref "*1") (pin "3") (pinfunction "VCC_3") (pintype "passive"))
      (node (ref "C1") (pin "2") (pinfunction "2_2") (pintype "passive"))
      (node (ref "C10") (pin "1") (pinfunction "1_1") (pintype "passive"))
      (node (ref "C13") (pin "2") (pinfunction "2_2") (pintype "passive"))
      (node (ref "C17") (pin "1") (pinfunction "1_1") (pintype "passive"))
      (node (ref "C2") (pin "2") (pinfunction "2_2") (pintype "passive"))
      (node (ref "C20") (pin "1") (pinfunction "1_1") (pintype "passive"))
      (node (ref "D2") (pin "2") (pinfunction "K_2") (pintype "passive"))
      (node (ref "D9") (pin "A") (pinfunction "A_A") (pintype "passive"))
      (node (ref "DPLC-L1") (pin "1") (pinfunction "5V_1") (pintype "passive"))
      (node (ref "J1") (pin "5") (pinfunction "5_5") (pintype "passive"))
      (node (ref "J15") (pin "1") (pinfunction "1_1") (pintype "passive"))
      (node (ref "J2") (pin "5") (pinfunction "5_5") (pintype "passive"))
      (node (ref "J5") (pin "4") (pinfunction "4_4") (pintype "passive"))
      (node (ref "J7") (pin "4") (pinfunction "4_4") (pintype "passive"))
      (node (ref "J9") (pin "1") (pinfunction "1_1") (pintype "passive"))
      (node (ref "U1") (pin "9") (pinfunction "COM_9") (pintype "passive"))
      (node (ref "U2") (pin "9") (pinfunction "COM_9") (pintype "passive"))
      (node (ref "U4") (pin "3") (pinfunction "VCC_3") (pintype "passive"))
      (node (ref "VR2") (pin "3") (pinfunction "Vout_3") (pintype "passive"))
      (node (ref "VR3") (pin "3") (pinfunction "Vin_3") (pintype "passive"))
      (node (ref "VR4") (pin "3") (pinfunction "Vout_3") (pintype "passive"))
      (node (ref "VR5") (pin "3") (pinfunction "Vin_3") (pintype "passive"))
      (node (ref "w1") (pin "1") (pinfunction "+_1") (pintype "passive"))
    )
    (net (code "54") (name "12V") (class "Default")
      (node (ref "C12") (pin "2") (pinfunction "2_2") (pintype "passive"))
      (node (ref "C16") (pin "1") (pinfunction "1_1") (pintype "passive"))
      (node (ref "C19") (pin "2") (pinfunction "2_2") (pintype "passive"))
      (node (ref "C9") (pin "1") (pinfunction "1_1") (pintype "passive"))
      (node (ref "D8") (pin "A") (pinfunction "A_A") (pintype "passive"))
      (node (ref "J3") (pin "2") (pinfunction "2_2") (pintype "passive"))
      (node (ref "VR1") (pin "3") (pinfunction "Vout_3") (pintype "passive"))
      (node (ref "VR2") (pin "1") (pinfunction "Vin_1") (pintype "passive"))
      (node (ref "VR4") (pin "1") (pinfunction "Vin_1") (pintype "passive"))
    )
    (net (code "55") (name "24V") (class "Default")
      (node (ref "C11") (pin "2") (pinfunction "2_2") (pintype "passive"))
      (node (ref "C8") (pin "1") (pinfunction "1_1") (pintype "passive"))
      (node (ref "D7") (pin "A") (pinfunction "A_A") (pintype "passive"))
      (node (ref "J12") (pin "1") (pinfunction "1_1") (pintype "passive"))
      (node (ref "VR1") (pin "1") (pinfunction "Vin_1") (pintype "passive"))
      (node (ref "W5") (pin "3") (pinfunction "3_3") (pintype "passive"))
    )
    (net (code "56") (name "GND") (class "Default")
      (node (ref "*1") (pin "1") (pinfunction "GND_1") (pintype "passive"))
      (node (ref "1") (pin "1") (pinfunction "1_1") (pintype "passive"))
      (node (ref "C1") (pin "1") (pinfunction "1_1") (pintype "passive"))
      (node (ref "C10") (pin "2") (pinfunction "2_2") (pintype "passive"))
      (node (ref "C11") (pin "1") (pinfunction "1_1") (pintype "passive"))
      (node (ref "C12") (pin "1") (pinfunction "1_1") (pintype "passive"))
      (node (ref "C13") (pin "1") (pinfunction "1_1") (pintype "passive"))
      (node (ref "C14") (pin "2") (pinfunction "2_2") (pintype "passive"))
      (node (ref "C15") (pin "2") (pinfunction "2_2") (pintype "passive"))
      (node (ref "C16") (pin "2") (pinfunction "2_2") (pintype "passive"))
      (node (ref "C17") (pin "2") (pinfunction "2_2") (pintype "passive"))
      (node (ref "C18") (pin "2") (pinfunction "2_2") (pintype "passive"))
      (node (ref "C19") (pin "1") (pinfunction "1_1") (pintype "passive"))
      (node (ref "C2") (pin "1") (pinfunction "1_1") (pintype "passive"))
      (node (ref "C20") (pin "2") (pinfunction "2_2") (pintype "passive"))
      (node (ref "C21") (pin "2") (pinfunction "2_2") (pintype "passive"))
      (node (ref "C27") (pin "1") (pinfunction "1_1") (pintype "passive"))
      (node (ref "C28") (pin "2") (pinfunction "2_2") (pintype "passive"))
      (node (ref "C3") (pin "1") (pinfunction "1_1") (pintype "passive"))
      (node (ref "C30") (pin "2") (pinfunction "2_2") (pintype "passive"))
      (node (ref "C31") (pin "1") (pinfunction "1_1") (pintype "passive"))
      (node (ref "C32") (pin "1") (pinfunction "1_1") (pintype "passive"))
      (node (ref "C33") (pin "1") (pinfunction "1_1") (pintype "passive"))
      (node (ref "C34") (pin "1") (pinfunction "1_1") (pintype "passive"))
      (node (ref "C35") (pin "1") (pinfunction "1_1") (pintype "passive"))
      (node (ref "C36") (pin "1") (pinfunction "1_1") (pintype "passive"))
      (node (ref "C37") (pin "2") (pinfunction "2_2") (pintype "passive"))
      (node (ref "C38") (pin "2") (pinfunction "2_2") (pintype "passive"))
      (node (ref "C4") (pin "1") (pinfunction "1_1") (pintype "passive"))
      (node (ref "C5") (pin "1") (pinfunction "1_1") (pintype "passive"))
      (node (ref "C6") (pin "1") (pinfunction "1_1") (pintype "passive"))
      (node (ref "C7") (pin "1") (pinfunction "1_1") (pintype "passive"))
      (node (ref "C8") (pin "2") (pinfunction "2_2") (pintype "passive"))
      (node (ref "C9") (pin "2") (pinfunction "2_2") (pintype "passive"))
      (node (ref "DPLC-L1") (pin "4") (pinfunction "GND_4") (pintype "passive"))
      (node (ref "J12") (pin "2") (pinfunction "2_2") (pintype "passive"))
      (node (ref "J15") (pin "4") (pinfunction "4_4") (pintype "passive"))
      (node (ref "J3") (pin "1") (pinfunction "1_1") (pintype "passive"))
      (node (ref "J5") (pin "1") (pinfunction "1_1") (pintype "passive"))
      (node (ref "J7") (pin "1") (pinfunction "1_1") (pintype "passive"))
      (node (ref "J8") (pin "1") (pinfunction "1_1") (pintype "passive"))
      (node (ref "J8") (pin "2") (pinfunction "2_2") (pintype "passive"))
      (node (ref "J8") (pin "3") (pinfunction "3_3") (pintype "passive"))
      (node (ref "J8") (pin "4") (pinfunction "4_4") (pintype "passive"))
      (node (ref "J9") (pin "6") (pinfunction "6_6") (pintype "passive"))
      (node (ref "R13") (pin "1") (pinfunction "1_1") (pintype "passive"))
      (node (ref "R14") (pin "1") (pinfunction "1_1") (pintype "passive"))
      (node (ref "R15") (pin "2") (pinfunction "2_2") (pintype "passive"))
      (node (ref "R16") (pin "1") (pinfunction "1_1") (pintype "passive"))
      (node (ref "R17") (pin "1") (pinfunction "1_1") (pintype "passive"))
      (node (ref "R18") (pin "1") (pinfunction "1_1") (pintype "passive"))
      (node (ref "R19") (pin "1") (pinfunction "1_1") (pintype "passive"))
      (node (ref "R2") (pin "2") (pinfunction "2_2") (pintype "passive"))
      (node (ref "R37") (pin "1") (pinfunction "1_1") (pintype "passive"))
      (node (ref "R39") (pin "2") (pinfunction "2_2") (pintype "passive"))
      (node (ref "R4") (pin "2") (pinfunction "2_2") (pintype "passive"))
      (node (ref "R6") (pin "2") (pinfunction "2_2") (pintype "passive"))
      (node (ref "R8") (pin "1") (pinfunction "1_1") (pintype "passive"))
      (node (ref "RP3") (pin "5") (pinfunction "5_5") (pintype "passive"))
      (node (ref "RP4") (pin "1") (pinfunction "1_1") (pintype "passive"))
      (node (ref "RP4") (pin "2") (pinfunction "2_2") (pintype "passive"))
      (node (ref "RP4") (pin "3") (pinfunction "3_3") (pintype "passive"))
      (node (ref "RP4") (pin "4") (pinfunction "4_4") (pintype "passive"))
      (node (ref "S1") (pin "5") (pinfunction "5_5") (pintype "passive"))
      (node (ref "S1") (pin "6") (pinfunction "6_6") (pintype "passive"))
      (node (ref "S1") (pin "7") (pinfunction "7_7") (pintype "passive"))
      (node (ref "S1") (pin "8") (pinfunction "8_8") (pintype "passive"))
      (node (ref "S2") (pin "1") (pinfunction "COMMON_1") (pintype "passive"))
      (node (ref "U1") (pin "8") (pinfunction "GND_8") (pintype "power_in"))
      (node (ref "U2") (pin "8") (pinfunction "GND_8") (pintype "power_in"))
      (node (ref "U3") (pin "12") (pinfunction "VSSA_12") (pintype "power_in"))
      (node (ref "U3") (pin "18") (pinfunction "VSS_4_18") (pintype "power_in"))
      (node (ref "U3") (pin "31") (pinfunction "VSS_1_31") (pintype "power_in"))
      (node (ref "U3") (pin "47") (pinfunction "VSS_2_47") (pintype "power_in"))
      (node (ref "U3") (pin "63") (pinfunction "VSS_3_63") (pintype "power_in"))
      (node (ref "U4") (pin "2") (pinfunction "GND_2") (pintype "passive"))
      (node (ref "U4") (pin "8") (pinfunction "S_8") (pintype "passive"))
      (node (ref "U5") (pin "10") (pinfunction "N.C._10") (pintype "passive"))
      (node (ref "U5") (pin "11") (pinfunction "N.C._11") (pintype "passive"))
      (node (ref "U5") (pin "12") (pinfunction "N.C._12") (pintype "passive"))
      (node (ref "U5") (pin "13") (pinfunction "GND_13") (pintype "passive"))
      (node (ref "U5") (pin "5") (pinfunction "N.C._5") (pintype "passive"))
      (node (ref "U5") (pin "6") (pinfunction "N.C._6") (pintype "passive"))
      (node (ref "U5") (pin "7") (pinfunction "N.C._7") (pintype "passive"))
      (node (ref "U5") (pin "8") (pinfunction "N.C._8") (pintype "passive"))
      (node (ref "U5") (pin "9") (pinfunction "N.C._9") (pintype "passive"))
      (node (ref "U6") (pin "14") (pinfunction "AGND_14") (pintype "passive"))
      (node (ref "U6") (pin "16") (pinfunction "AGND_16") (pintype "passive"))
      (node (ref "U6") (pin "19") (pinfunction "AGND_19") (pintype "passive"))
      (node (ref "U6") (pin "29") (pinfunction "GND_29") (pintype "passive"))
      (node (ref "U6") (pin "3") (pinfunction "AGND_3") (pintype "passive"))
      (node (ref "U6") (pin "48") (pinfunction "AGND_48") (pintype "passive"))
      (node (ref "VR1") (pin "2") (pinfunction "GND_2") (pintype "passive"))
      (node (ref "VR2") (pin "2") (pinfunction "GND_2") (pintype "passive"))
      (node (ref "VR3") (pin "1") (pinfunction "GND_1") (pintype "passive"))
      (node (ref "VR4") (pin "2") (pinfunction "GND_2") (pintype "passive"))
      (node (ref "VR5") (pin "1") (pinfunction "GND_1") (pintype "passive"))
      (node (ref "W5") (pin "4") (pinfunction "4_4") (pintype "passive"))
    )
    (net (code "57") (name "Net-(*1-OFF)") (class "Default")
      (node (ref "*1") (pin "4") (pinfunction "OFF_4") (pintype "passive"))
      (node (ref "D1") (pin "K") (pinfunction "K_K") (pintype "passive"))
    )
    (net (code "58") (name "Net-(*1-ON)") (class "Default")
      (node (ref "*1") (pin "5") (pinfunction "ON_5") (pintype "passive"))
      (node (ref "D3") (pin "K") (pinfunction "K_K") (pintype "passive"))
    )
    (net (code "59") (name "Net-(D1-PadA)") (class "Default")
      (node (ref "D1") (pin "A") (pinfunction "A_A") (pintype "passive"))
      (node (ref "R7") (pin "2") (pinfunction "2_2") (pintype "passive"))
    )
    (net (code "60") (name "Net-(D2-A)") (class "Default")
      (node (ref "D2") (pin "1") (pinfunction "A_1") (pintype "passive"))
      (node (ref "Q3") (pin "3") (pinfunction "C_3") (pintype "passive"))
    )
    (net (code "61") (name "Net-(D3-PadA)") (class "Default")
      (node (ref "D3") (pin "A") (pinfunction "A_A") (pintype "passive"))
      (node (ref "R11") (pin "2") (pinfunction "2_2") (pintype "passive"))
    )
    (net (code "62") (name "Net-(D4-PadK)") (class "Default")
      (node (ref "D4") (pin "K") (pinfunction "K_K") (pintype "passive"))
      (node (ref "R13") (pin "2") (pinfunction "2_2") (pintype "passive"))
    )
    (net (code "63") (name "Net-(D5-PadK)") (class "Default")
      (node (ref "D5") (pin "K") (pinfunction "K_K") (pintype "passive"))
      (node (ref "R14") (pin "2") (pinfunction "2_2") (pintype "passive"))
    )
    (net (code "64") (name "Net-(D6-A)") (class "Default")
      (node (ref "D6") (pin "1") (pinfunction "A_1") (pintype "passive"))
      (node (ref "R10") (pin "2") (pinfunction "2_2") (pintype "passive"))
    )
    (net (code "65") (name "Net-(D7-PadK)") (class "Default")
      (node (ref "D7") (pin "K") (pinfunction "K_K") (pintype "passive"))
      (node (ref "R16") (pin "2") (pinfunction "2_2") (pintype "passive"))
    )
    (net (code "66") (name "Net-(D8-PadK)") (class "Default")
      (node (ref "D8") (pin "K") (pinfunction "K_K") (pintype "passive"))
      (node (ref "R17") (pin "2") (pinfunction "2_2") (pintype "passive"))
    )
    (net (code "67") (name "Net-(D9-PadK)") (class "Default")
      (node (ref "D9") (pin "K") (pinfunction "K_K") (pintype "passive"))
      (node (ref "R18") (pin "2") (pinfunction "2_2") (pintype "passive"))
    )
    (net (code "68") (name "Net-(D10-PadK)") (class "Default")
      (node (ref "D10") (pin "K") (pinfunction "K_K") (pintype "passive"))
      (node (ref "R19") (pin "2") (pinfunction "2_2") (pintype "passive"))
    )
    (net (code "69") (name "Net-(J10-GND-Pad1)") (class "Default")
      (node (ref "J10") (pin "1") (pinfunction "GND_1") (pintype "passive"))
      (node (ref "R11") (pin "1") (pinfunction "1_1") (pintype "passive"))
    )
    (net (code "70") (name "Net-(J13-CHS)") (class "Default")
      (node (ref "C32") (pin "2") (pinfunction "2_2") (pintype "passive"))
      (node (ref "C33") (pin "2") (pinfunction "2_2") (pintype "passive"))
      (node (ref "J13") (pin "13") (pinfunction "SHILD_13") (pintype "passive"))
      (node (ref "J13") (pin "14") (pinfunction "SHILD_14") (pintype "passive"))
      (node (ref "J13") (pin "8") (pinfunction "CHS_8") (pintype "passive"))
    )
    (net (code "71") (name "Net-(J13-D1-)") (class "Default")
      (node (ref "J13") (pin "10") (pinfunction "D1-_10") (pintype "passive"))
      (node (ref "R36") (pin "2") (pinfunction "2_2") (pintype "passive"))
    )
    (net (code "72") (name "Net-(J13-D2-)") (class "Default")
      (node (ref "J13") (pin "11") (pinfunction "D2-_11") (pintype "passive"))
      (node (ref "R38") (pin "2") (pinfunction "2_2") (pintype "passive"))
    )
    (net (code "73") (name "Net-(J13-RCT)") (class "Default")
      (node (ref "C34") (pin "2") (pinfunction "2_2") (pintype "passive"))
      (node (ref "J13") (pin "5") (pinfunction "RCT_5") (pintype "passive"))
      (node (ref "R25") (pin "1") (pinfunction "1_1") (pintype "passive"))
      (node (ref "R34") (pin "1") (pinfunction "1_1") (pintype "passive"))
    )
    (net (code "74") (name "Net-(J13-RDN)") (class "Default")
      (node (ref "C29") (pin "2") (pinfunction "2_2") (pintype "passive"))
      (node (ref "J13") (pin "6") (pinfunction "RDN_6") (pintype "passive"))
    )
    (net (code "75") (name "Net-(J13-RDP)") (class "Default")
      (node (ref "C26") (pin "2") (pinfunction "2_2") (pintype "passive"))
      (node (ref "J13") (pin "3") (pinfunction "RDP_3") (pintype "passive"))
    )
    (net (code "76") (name "Net-(J13-TCT)") (class "Default")
      (node (ref "C27") (pin "2") (pinfunction "2_2") (pintype "passive"))
      (node (ref "J13") (pin "4") (pinfunction "TCT_4") (pintype "passive"))
      (node (ref "R29") (pin "1") (pinfunction "1_1") (pintype "passive"))
    )
    (net (code "77") (name "Net-(P1-Pad1)") (class "Default")
      (node (ref "P1") (pin "1") (pinfunction "1_1") (pintype "passive"))
      (node (ref "R7") (pin "1") (pinfunction "1_1") (pintype "passive"))
    )
    (net (code "78") (name "Net-(Q1-B)") (class "Default")
      (node (ref "Q1") (pin "1") (pinfunction "B_1") (pintype "passive"))
      (node (ref "R3") (pin "2") (pinfunction "2_2") (pintype "passive"))
    )
    (net (code "79") (name "Net-(Q1-C)") (class "Default")
      (node (ref "J4") (pin "2") (pinfunction "2_2") (pintype "passive"))
      (node (ref "Q1") (pin "3") (pinfunction "C_3") (pintype "passive"))
    )
    (net (code "80") (name "Net-(Q1-E)") (class "Default")
      (node (ref "Q1") (pin "2") (pinfunction "E_2") (pintype "passive"))
      (node (ref "R4") (pin "1") (pinfunction "1_1") (pintype "passive"))
    )
    (net (code "81") (name "Net-(Q2-B)") (class "Default")
      (node (ref "Q2") (pin "1") (pinfunction "B_1") (pintype "passive"))
      (node (ref "R5") (pin "2") (pinfunction "2_2") (pintype "passive"))
    )
    (net (code "82") (name "Net-(Q2-C)") (class "Default")
      (node (ref "Q2") (pin "3") (pinfunction "C_3") (pintype "passive"))
      (node (ref "w1") (pin "2") (pintype "passive"))
    )
    (net (code "83") (name "Net-(Q2-E)") (class "Default")
      (node (ref "Q2") (pin "2") (pinfunction "E_2") (pintype "passive"))
      (node (ref "R6") (pin "1") (pinfunction "1_1") (pintype "passive"))
    )
    (net (code "84") (name "Net-(Q3-B)") (class "Default")
      (node (ref "Q3") (pin "1") (pinfunction "B_1") (pintype "passive"))
      (node (ref "R12") (pin "2") (pinfunction "2_2") (pintype "passive"))
    )
    (net (code "85") (name "Net-(Q3-E)") (class "Default")
      (node (ref "Q3") (pin "2") (pinfunction "E_2") (pintype "passive"))
      (node (ref "R15") (pin "1") (pinfunction "1_1") (pintype "passive"))
    )
    (net (code "86") (name "Net-(R39-Pad1)") (class "Default")
      (node (ref "R39") (pin "1") (pinfunction "1_1") (pintype "passive"))
      (node (ref "U6") (pin "23") (pinfunction "RSVD_23") (pintype "passive"))
    )
    (net (code "87") (name "Net-(RP3-Pad4)") (class "Default")
      (node (ref "RP3") (pin "4") (pinfunction "4_4") (pintype "passive"))
      (node (ref "U6") (pin "42") (pinfunction "RSVD_42") (pintype "passive"))
    )
    (net (code "88") (name "Net-(RP4-Pad5)") (class "Default")
      (node (ref "RP4") (pin "5") (pinfunction "5_5") (pintype "passive"))
      (node (ref "U6") (pin "41") (pinfunction "RSVD_41") (pintype "passive"))
    )
    (net (code "89") (name "Net-(RP4-Pad6)") (class "Default")
      (node (ref "RP4") (pin "6") (pinfunction "6_6") (pintype "passive"))
      (node (ref "U6") (pin "40") (pinfunction "RSVD_40") (pintype "passive"))
    )
    (net (code "90") (name "Net-(RP4-Pad7)") (class "Default")
      (node (ref "RP4") (pin "7") (pinfunction "7_7") (pintype "passive"))
      (node (ref "U6") (pin "39") (pinfunction "RSVD_39") (pintype "passive"))
    )
    (net (code "91") (name "Net-(RP4-Pad8)") (class "Default")
      (node (ref "RP4") (pin "8") (pinfunction "8_8") (pintype "passive"))
      (node (ref "U6") (pin "38") (pinfunction "RSVD_38") (pintype "passive"))
    )
    (net (code "92") (name "Net-(S2-NO)") (class "Default")
      (node (ref "C5") (pin "2") (pinfunction "2_2") (pintype "passive"))
      (node (ref "R9") (pin "2") (pinfunction "2_2") (pintype "passive"))
      (node (ref "S2") (pin "2") (pinfunction "NO_2") (pintype "passive"))
      (node (ref "U3") (pin "7") (pinfunction "NRST_7") (pintype "bidirectional"))
    )
    (net (code "93") (name "Net-(U1-OUT1)") (class "Default")
      (node (ref "J1") (pin "1") (pinfunction "1_1") (pintype "passive"))
      (node (ref "U1") (pin "16") (pinfunction "OUT1_16") (pintype "open_collector"))
    )
    (net (code "94") (name "Net-(U1-OUT2)") (class "Default")
      (node (ref "J1") (pin "2") (pinfunction "2_2") (pintype "passive"))
      (node (ref "U1") (pin "15") (pinfunction "OUT2_15") (pintype "open_collector"))
    )
    (net (code "95") (name "Net-(U1-OUT3)") (class "Default")
      (node (ref "J1") (pin "3") (pinfunction "3_3") (pintype "passive"))
      (node (ref "U1") (pin "14") (pinfunction "OUT3_14") (pintype "open_collector"))
    )
    (net (code "96") (name "Net-(U1-OUT4)") (class "Default")
      (node (ref "J1") (pin "4") (pinfunction "4_4") (pintype "passive"))
      (node (ref "U1") (pin "13") (pinfunction "OUT4_13") (pintype "open_collector"))
    )
    (net (code "97") (name "Net-(U2-OUT1)") (class "Default")
      (node (ref "J2") (pin "1") (pinfunction "1_1") (pintype "passive"))
      (node (ref "U2") (pin "16") (pinfunction "OUT1_16") (pintype "open_collector"))
    )
    (net (code "98") (name "Net-(U2-OUT2)") (class "Default")
      (node (ref "J2") (pin "2") (pinfunction "2_2") (pintype "passive"))
      (node (ref "U2") (pin "15") (pinfunction "OUT2_15") (pintype "open_collector"))
    )
    (net (code "99") (name "Net-(U2-OUT3)") (class "Default")
      (node (ref "J2") (pin "3") (pinfunction "3_3") (pintype "passive"))
      (node (ref "U2") (pin "14") (pinfunction "OUT3_14") (pintype "open_collector"))
    )
    (net (code "100") (name "Net-(U2-OUT4)") (class "Default")
      (node (ref "J2") (pin "4") (pinfunction "4_4") (pintype "passive"))
      (node (ref "U2") (pin "13") (pinfunction "OUT4_13") (pintype "open_collector"))
    )
    (net (code "101") (name "Net-(U3-BOOT0)") (class "Default")
      (node (ref "R8") (pin "2") (pinfunction "2_2") (pintype "passive"))
      (node (ref "U3") (pin "60") (pinfunction "BOOT0_60") (pintype "input"))
    )
    (net (code "102") (name "Net-(U3-OSC_IN{slash}PD0)") (class "Default")
      (node (ref "C3") (pin "2") (pinfunction "2_2") (pintype "passive"))
      (node (ref "U3") (pin "5") (pinfunction "OSC_IN/PD0_5") (pintype "input"))
      (node (ref "Y1") (pin "2") (pinfunction "OSC2_2") (pintype "passive"))
    )
    (net (code "103") (name "Net-(U3-OSC_OUT{slash}PD1)") (class "Default")
      (node (ref "C4") (pin "2") (pinfunction "2_2") (pintype "passive"))
      (node (ref "U3") (pin "6") (pinfunction "OSC_OUT/PD1_6") (pintype "output"))
      (node (ref "Y1") (pin "1") (pinfunction "OSC1_1") (pintype "passive"))
    )
    (net (code "104") (name "Net-(U3-PB2{slash}BOOT1)") (class "Default")
      (node (ref "R2") (pin "1") (pinfunction "1_1") (pintype "passive"))
      (node (ref "U3") (pin "28") (pinfunction "PB2/BOOT1_28") (pintype "bidirectional"))
    )
    (net (code "105") (name "Net-(U3-PC0)") (class "Default")
      (node (ref "RP1") (pin "8") (pinfunction "8_8") (pintype "passive"))
      (node (ref "S1") (pin "1") (pinfunction "1_1") (pintype "passive"))
      (node (ref "U3") (pin "8") (pinfunction "PC0_8") (pintype "bidirectional"))
    )
    (net (code "106") (name "Net-(U3-PC1)") (class "Default")
      (node (ref "RP1") (pin "7") (pinfunction "7_7") (pintype "passive"))
      (node (ref "S1") (pin "2") (pinfunction "2_2") (pintype "passive"))
      (node (ref "U3") (pin "9") (pinfunction "PC1_9") (pintype "bidirectional"))
    )
    (net (code "107") (name "Net-(U3-PC2)") (class "Default")
      (node (ref "RP1") (pin "6") (pinfunction "6_6") (pintype "passive"))
      (node (ref "S1") (pin "3") (pinfunction "3_3") (pintype "passive"))
      (node (ref "U3") (pin "10") (pinfunction "PC2_10") (pintype "bidirectional"))
    )
    (net (code "108") (name "Net-(U3-PC3)") (class "Default")
      (node (ref "RP1") (pin "5") (pinfunction "5_5") (pintype "passive"))
      (node (ref "S1") (pin "4") (pinfunction "4_4") (pintype "passive"))
      (node (ref "U3") (pin "11") (pinfunction "PC3_11") (pintype "bidirectional"))
    )
    (net (code "109") (name "Net-(U4-CANH)") (class "Default")
      (node (ref "J6") (pin "2") (pinfunction "2_2") (pintype "passive"))
      (node (ref "R1") (pin "1") (pinfunction "1_1") (pintype "passive"))
      (node (ref "U4") (pin "7") (pinfunction "CANH_7") (pintype "passive"))
    )
    (net (code "110") (name "Net-(U4-CANL)") (class "Default")
      (node (ref "J6") (pin "1") (pinfunction "1_1") (pintype "passive"))
      (node (ref "R1") (pin "2") (pinfunction "2_2") (pintype "passive"))
      (node (ref "U4") (pin "6") (pinfunction "CANL_6") (pintype "passive"))
    )
    (net (code "111") (name "Net-(U6-1V2O)") (class "Default")
      (node (ref "C37") (pin "1") (pinfunction "1_1") (pintype "passive"))
      (node (ref "U6") (pin "22") (pinfunction "1V2O_22") (pintype "passive"))
    )
    (net (code "112") (name "Net-(U6-EXRES1)") (class "Default")
      (node (ref "R37") (pin "2") (pinfunction "2_2") (pintype "passive"))
      (node (ref "U6") (pin "10") (pinfunction "EXRES1_10") (pintype "passive"))
    )
    (net (code "113") (name "Net-(U6-TOCAP)") (class "Default")
      (node (ref "C38") (pin "1") (pinfunction "1_1") (pintype "passive"))
      (node (ref "U6") (pin "20") (pinfunction "TOCAP_20") (pintype "passive"))
    )
    (net (code "114") (name "Net-(U6-XI{slash}CLCKIN)") (class "Default")
      (node (ref "C30") (pin "1") (pinfunction "1_1") (pintype "passive"))
      (node (ref "R33") (pin "1") (pinfunction "1_1") (pintype "passive"))
      (node (ref "U6") (pin "30") (pinfunction "XI/CLCKIN_30") (pintype "passive"))
      (node (ref "Y2") (pin "1") (pinfunction "OSC1_1") (pintype "passive"))
    )
    (net (code "115") (name "Net-(U6-XO)") (class "Default")
      (node (ref "C28") (pin "1") (pinfunction "1_1") (pintype "passive"))
      (node (ref "R33") (pin "2") (pinfunction "2_2") (pintype "passive"))
      (node (ref "U6") (pin "31") (pinfunction "XO_31") (pintype "passive"))
      (node (ref "Y2") (pin "3") (pinfunction "OSC2_3") (pintype "passive"))
    )
    (net (code "116") (name "unconnected-(DPLC-L1-Pad5)") (class "Default")
      (node (ref "DPLC-L1") (pin "5") (pinfunction "5_5") (pintype "passive"))
    )
    (net (code "117") (name "unconnected-(J13-NC-Pad7)") (class "Default")
      (node (ref "J13") (pin "7") (pinfunction "NC_7") (pintype "passive"))
    )
    (net (code "118") (name "unconnected-(U1-IN5-Pad5)") (class "Default")
      (node (ref "U1") (pin "5") (pinfunction "IN5_5") (pintype "input"))
    )
    (net (code "119") (name "unconnected-(U1-IN6-Pad6)") (class "Default")
      (node (ref "U1") (pin "6") (pinfunction "IN6_6") (pintype "input"))
    )
    (net (code "120") (name "unconnected-(U1-IN7-Pad7)") (class "Default")
      (node (ref "U1") (pin "7") (pinfunction "IN7_7") (pintype "input"))
    )
    (net (code "121") (name "unconnected-(U1-OUT5-Pad12)") (class "Default")
      (node (ref "U1") (pin "12") (pinfunction "OUT5_12") (pintype "open_collector"))
    )
    (net (code "122") (name "unconnected-(U1-OUT6-Pad11)") (class "Default")
      (node (ref "U1") (pin "11") (pinfunction "OUT6_11") (pintype "open_collector"))
    )
    (net (code "123") (name "unconnected-(U1-OUT7-Pad10)") (class "Default")
      (node (ref "U1") (pin "10") (pinfunction "OUT7_10") (pintype "open_collector"))
    )
    (net (code "124") (name "unconnected-(U2-IN5-Pad5)") (class "Default")
      (node (ref "U2") (pin "5") (pinfunction "IN5_5") (pintype "input"))
    )
    (net (code "125") (name "unconnected-(U2-IN6-Pad6)") (class "Default")
      (node (ref "U2") (pin "6") (pinfunction "IN6_6") (pintype "input"))
    )
    (net (code "126") (name "unconnected-(U2-IN7-Pad7)") (class "Default")
      (node (ref "U2") (pin "7") (pinfunction "IN7_7") (pintype "input"))
    )
    (net (code "127") (name "unconnected-(U2-OUT5-Pad12)") (class "Default")
      (node (ref "U2") (pin "12") (pinfunction "OUT5_12") (pintype "open_collector"))
    )
    (net (code "128") (name "unconnected-(U2-OUT6-Pad11)") (class "Default")
      (node (ref "U2") (pin "11") (pinfunction "OUT6_11") (pintype "open_collector"))
    )
    (net (code "129") (name "unconnected-(U2-OUT7-Pad10)") (class "Default")
      (node (ref "U2") (pin "10") (pinfunction "OUT7_10") (pintype "open_collector"))
    )
    (net (code "130") (name "unconnected-(U3-PA0-WKUP-Pad14)") (class "Default")
      (node (ref "U3") (pin "14") (pinfunction "PA0-WKUP_14") (pintype "bidirectional"))
    )
    (net (code "131") (name "unconnected-(U3-PA15{slash}JTDI-Pad50)") (class "Default")
      (node (ref "U3") (pin "50") (pinfunction "PA15/JTDI_50") (pintype "bidirectional"))
    )
    (net (code "132") (name "unconnected-(U3-PB3{slash}JTDO-Pad55)") (class "Default")
      (node (ref "U3") (pin "55") (pinfunction "PB3/JTDO_55") (pintype "bidirectional"))
    )
    (net (code "133") (name "unconnected-(U3-PC13-TAMPER-RTC-Pad2)") (class "Default")
      (node (ref "U3") (pin "2") (pinfunction "PC13-TAMPER-RTC_2") (pintype "bidirectional"))
    )
    (net (code "134") (name "unconnected-(U3-PC14-OSC32_IN-Pad3)") (class "Default")
      (node (ref "U3") (pin "3") (pinfunction "PC14-OSC32_IN_3") (pintype "bidirectional"))
    )
    (net (code "135") (name "unconnected-(U3-PC15-OSC32_OUT-Pad4)") (class "Default")
      (node (ref "U3") (pin "4") (pinfunction "PC15-OSC32_OUT_4") (pintype "bidirectional"))
    )
    (net (code "136") (name "unconnected-(U3-PD2-Pad54)") (class "Default")
      (node (ref "U3") (pin "54") (pinfunction "PD2_54") (pintype "bidirectional"))
    )
    (net (code "137") (name "unconnected-(U4-n.c.-Pad5)") (class "Default")
      (node (ref "U4") (pin "5") (pinfunction "n.c._5") (pintype "passive"))
    )
    (net (code "138") (name "unconnected-(U5-~{RST}-Pad4)") (class "Default")
      (node (ref "U5") (pin "4") (pinfunction "~{RST}_4") (pintype "passive"))
    )
    (net (code "139") (name "unconnected-(U6-AGND-Pad9)") (class "Default")
      (node (ref "U6") (pin "9") (pinfunction "AGND_9") (pintype "passive"))
    )
    (net (code "140") (name "unconnected-(U6-AVDD-Pad8)") (class "Default")
      (node (ref "U6") (pin "8") (pinfunction "AVDD_8") (pintype "passive"))
    )
    (net (code "141") (name "unconnected-(U6-AVDD-Pad11)") (class "Default")
      (node (ref "U6") (pin "11") (pinfunction "AVDD_11") (pintype "passive"))
    )
    (net (code "142") (name "unconnected-(U6-DNC-Pad7)") (class "Default")
      (node (ref "U6") (pin "7") (pinfunction "DNC_7") (pintype "passive"))
    )
    (net (code "143") (name "unconnected-(U6-DUPLED-Pad26)") (class "Default")
      (node (ref "U6") (pin "26") (pinfunction "DUPLED_26") (pintype "passive"))
    )
    (net (code "144") (name "unconnected-(U6-NC-Pad12)") (class "Default")
      (node (ref "U6") (pin "12") (pinfunction "NC_12") (pintype "passive"))
    )
    (net (code "145") (name "unconnected-(U6-NC-Pad13)") (class "Default")
      (node (ref "U6") (pin "13") (pinfunction "NC_13") (pintype "passive"))
    )
    (net (code "146") (name "unconnected-(U6-NC-Pad46)") (class "Default")
      (node (ref "U6") (pin "46") (pinfunction "NC_46") (pintype "passive"))
    )
    (net (code "147") (name "unconnected-(U6-NC-Pad47)") (class "Default")
      (node (ref "U6") (pin "47") (pinfunction "NC_47") (pintype "passive"))
    )
    (net (code "148") (name "unconnected-(U6-SPDLED-Pad24)") (class "Default")
      (node (ref "U6") (pin "24") (pinfunction "SPDLED_24") (pintype "passive+no_connect"))
    )
    (net (code "149") (name "unconnected-(U6-VBG-Pad18)") (class "Default")
      (node (ref "U6") (pin "18") (pinfunction "VBG_18") (pintype "passive"))
    )
  )
)
